# OLED_MODEL.net
KiCad netlist of a schematic drawn in Altium Designer
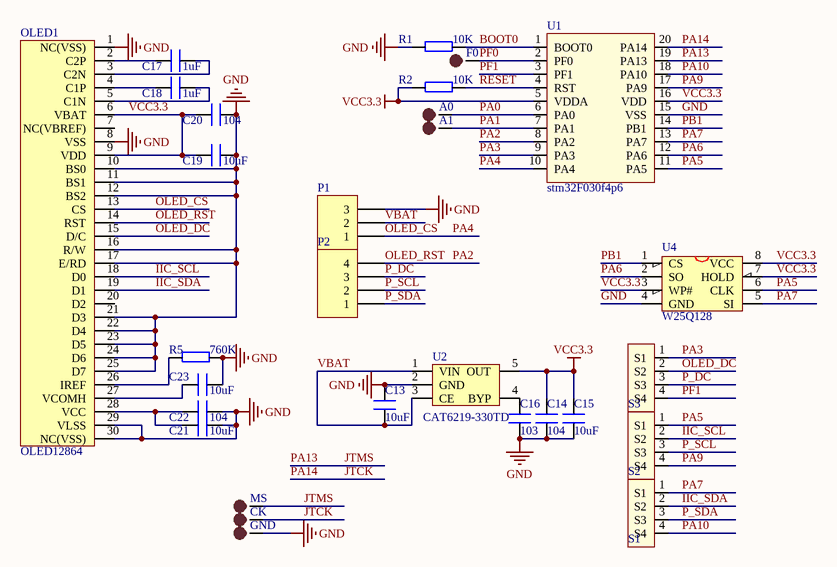
[diagram p0: OLED_MODEL.SchDoc]

(export (version "E")
  (design (tool "Eeschema 10.0.6"))
  (components
    (comp (ref "A0")
      (value "TEST POINT")
      (footprint "TP-1.5")
      (description "测试点")
      (libsource (lib "STM32F767核心板封装库") (part "TEST-POINT"))
    )
    (comp (ref "A1")
      (value "TEST POINT")
      (footprint "TP-1.5")
      (description "测试点")
      (libsource (lib "STM32F767核心板封装库") (part "TEST-POINT"))
    )
    (comp (ref "C13")
      (value "10uF")
      (footprint "C 0603_L")
      (libsource (lib "WarShip V3 STM32103封装库") (part "C"))
    )
    (comp (ref "C14")
      (value "104")
      (footprint "C 0603_L")
      (libsource (lib "WarShip V3 STM32103封装库") (part "C"))
    )
    (comp (ref "C15")
      (value "10uF")
      (footprint "C 0603_L")
      (libsource (lib "WarShip V3 STM32103封装库") (part "C"))
    )
    (comp (ref "C16")
      (value "103")
      (footprint "C 0603_L")
      (libsource (lib "WarShip V3 STM32103封装库") (part "C"))
    )
    (comp (ref "C17")
      (value "1uF")
      (footprint "C 0603_L")
      (libsource (lib "WarShip V3 STM32103封装库") (part "C"))
    )
    (comp (ref "C18")
      (value "1uF")
      (footprint "C 0603_L")
      (libsource (lib "WarShip V3 STM32103封装库") (part "C"))
    )
    (comp (ref "C19")
      (value "10uF")
      (footprint "C 0603_L")
      (libsource (lib "WarShip V3 STM32103封装库") (part "C"))
    )
    (comp (ref "C20")
      (value "104")
      (footprint "C 0603_L")
      (libsource (lib "WarShip V3 STM32103封装库") (part "C"))
    )
    (comp (ref "C21")
      (value "10uF")
      (footprint "C 0603_L")
      (libsource (lib "WarShip V3 STM32103封装库") (part "C"))
    )
    (comp (ref "C22")
      (value "104")
      (footprint "C 0603_L")
      (libsource (lib "WarShip V3 STM32103封装库") (part "C"))
    )
    (comp (ref "C23")
      (value "10uF")
      (footprint "C 0603_L")
      (libsource (lib "WarShip V3 STM32103封装库") (part "C"))
    )
    (comp (ref "CK")
      (value "TEST POINT")
      (footprint "TP-1.5")
      (description "测试点")
      (libsource (lib "STM32F767核心板封装库") (part "TEST-POINT"))
    )
    (comp (ref "F0")
      (value "TEST POINT")
      (footprint "TP-1.5")
      (description "测试点")
      (libsource (lib "STM32F767核心板封装库") (part "TEST-POINT"))
    )
    (comp (ref "GND")
      (value "TEST POINT")
      (footprint "TP-1.5")
      (description "测试点")
      (libsource (lib "STM32F767核心板封装库") (part "TEST-POINT"))
    )
    (comp (ref "MS")
      (value "TEST POINT")
      (footprint "TP-1.5")
      (description "测试点")
      (libsource (lib "STM32F767核心板封装库") (part "TEST-POINT"))
    )
    (comp (ref "OLED1")
      (value "OLED12864")
      (footprint "OLED_0.96")
      (libsource (lib "OLED模块封装库") (part "OLED12864"))
    )
    (comp (ref "P1")
      (value "Header 3")
      (footprint "HDR2.54-LI-3P")
      (description "Header, 3-Pin")
      (fields (field (name "PUBLISHER") "Altium Limited"))
      (libsource (lib "STA326_V1.7") (part "Header 3"))
    )
    (comp (ref "P2")
      (value "Header 4")
      (footprint "HDR2.54-LI-4P")
      (description "Header, 4-Pin")
      (fields (field (name "PUBLISHER") "Altium Limited"))
      (libsource (lib "STA326_V1.7") (part "Header 4"))
    )
    (comp (ref "R1")
      (value "10K")
      (footprint "R 0603_L")
      (libsource (lib "WarShip V3 STM32103封装库") (part "R"))
    )
    (comp (ref "R2")
      (value "10K")
      (footprint "R 0603_L")
      (libsource (lib "WarShip V3 STM32103封装库") (part "R"))
    )
    (comp (ref "R5")
      (value "760K")
      (footprint "R 0603_L")
      (libsource (lib "WarShip V3 STM32103封装库") (part "R"))
    )
    (comp (ref "S1")
      (value "selecter")
      (footprint "selector_4")
      (libsource (lib "oled_model") (part "selector_4"))
    )
    (comp (ref "S2")
      (value "selecter")
      (footprint "selector_4")
      (libsource (lib "oled_model") (part "selector_4"))
    )
    (comp (ref "S3")
      (value "selecter")
      (footprint "selector_4")
      (libsource (lib "oled_model") (part "selector_4"))
    )
    (comp (ref "U1")
      (value "stm32F030f4p6")
      (footprint "TSSOP20_N")
      (libsource (lib "oled_model") (part "stm32f030"))
    )
    (comp (ref "U2")
      (value "CAT6219-330TD")
      (footprint "SOT23-5N")
      (description "3.3V 500mA LDO")
      (libsource (lib "STM32H743核心板封装库") (part "CAT6219-330TD"))
    )
    (comp (ref "U4")
      (value "W25Q128")
      (footprint "SOIC-8")
      (description "W25X16;SST25VF016;MX25L1605")
      (libsource (lib "WarShip V3 STM32103封装库") (part "W25X16"))
    )
  )
  (nets
    (net (code "1") (name "/BOOT0") (class "Default")
      (node (ref "R1") (pin "1") (pintype "passive"))
      (node (ref "U1") (pin "1") (pinfunction "BOOT0_1") (pintype "passive"))
    )
    (net (code "2") (name "/IIC_SCL") (class "Default")
      (node (ref "OLED1") (pin "18") (pinfunction "D0_18") (pintype "passive"))
      (node (ref "S2") (pin "2") (pinfunction "S2_2") (pintype "passive"))
    )
    (net (code "3") (name "/IIC_SDA") (class "Default")
      (node (ref "OLED1") (pin "19") (pinfunction "D1_19") (pintype "passive"))
      (node (ref "S1") (pin "2") (pinfunction "S2_2") (pintype "passive"))
    )
    (net (code "4") (name "/JTCK") (class "Default")
      (node (ref "CK") (pin "1") (pinfunction "1_1") (pintype "passive"))
      (node (ref "U1") (pin "20") (pinfunction "PA14_20") (pintype "passive"))
    )
    (net (code "5") (name "/JTMS") (class "Default")
      (node (ref "MS") (pin "1") (pinfunction "1_1") (pintype "passive"))
      (node (ref "U1") (pin "19") (pinfunction "PA13_19") (pintype "passive"))
    )
    (net (code "6") (name "/OLED_CS") (class "Default")
      (node (ref "OLED1") (pin "13") (pinfunction "CS_13") (pintype "passive"))
      (node (ref "P1") (pin "1") (pinfunction "1_1") (pintype "passive"))
      (node (ref "U1") (pin "10") (pinfunction "PA4_10") (pintype "passive"))
    )
    (net (code "7") (name "/OLED_DC") (class "Default")
      (node (ref "OLED1") (pin "15") (pinfunction "D/C_15") (pintype "passive"))
      (node (ref "S3") (pin "2") (pinfunction "S2_2") (pintype "passive"))
    )
    (net (code "8") (name "/OLED_RST") (class "Default")
      (node (ref "OLED1") (pin "14") (pinfunction "RST_14") (pintype "passive"))
      (node (ref "P2") (pin "4") (pinfunction "4_4") (pintype "passive"))
      (node (ref "U1") (pin "8") (pinfunction "PA2_8") (pintype "passive"))
    )
    (net (code "9") (name "/PA0") (class "Default")
      (node (ref "A0") (pin "1") (pinfunction "1_1") (pintype "passive"))
      (node (ref "U1") (pin "6") (pinfunction "PA0_6") (pintype "passive"))
    )
    (net (code "10") (name "/PA1") (class "Default")
      (node (ref "A1") (pin "1") (pinfunction "1_1") (pintype "passive"))
      (node (ref "U1") (pin "7") (pinfunction "PA1_7") (pintype "passive"))
    )
    (net (code "11") (name "/PA3") (class "Default")
      (node (ref "S3") (pin "1") (pinfunction "S1_1") (pintype "passive"))
      (node (ref "U1") (pin "9") (pinfunction "PA3_9") (pintype "passive"))
    )
    (net (code "12") (name "/PA5") (class "Default")
      (node (ref "S2") (pin "1") (pinfunction "S1_1") (pintype "passive"))
      (node (ref "U1") (pin "11") (pinfunction "PA5_11") (pintype "passive"))
      (node (ref "U4") (pin "6") (pinfunction "CLK_6") (pintype "passive"))
    )
    (net (code "13") (name "/PA6") (class "Default")
      (node (ref "U1") (pin "12") (pinfunction "PA6_12") (pintype "passive"))
      (node (ref "U4") (pin "2") (pinfunction "SO_2") (pintype "passive"))
    )
    (net (code "14") (name "/PA7") (class "Default")
      (node (ref "S1") (pin "1") (pinfunction "S1_1") (pintype "passive"))
      (node (ref "U1") (pin "13") (pinfunction "PA7_13") (pintype "passive"))
      (node (ref "U4") (pin "5") (pinfunction "SI_5") (pintype "passive"))
    )
    (net (code "15") (name "/PA9") (class "Default")
      (node (ref "S2") (pin "4") (pinfunction "S4_4") (pintype "passive"))
      (node (ref "U1") (pin "17") (pinfunction "PA9_17") (pintype "passive"))
    )
    (net (code "16") (name "/PA10") (class "Default")
      (node (ref "S1") (pin "4") (pinfunction "S4_4") (pintype "passive"))
      (node (ref "U1") (pin "18") (pinfunction "PA10_18") (pintype "passive"))
    )
    (net (code "17") (name "/PB1") (class "Default")
      (node (ref "U1") (pin "14") (pinfunction "PB1_14") (pintype "passive"))
      (node (ref "U4") (pin "1") (pinfunction "CS_1") (pintype "passive"))
    )
    (net (code "18") (name "/PF0") (class "Default")
      (node (ref "F0") (pin "1") (pinfunction "1_1") (pintype "passive"))
      (node (ref "U1") (pin "2") (pinfunction "PF0_2") (pintype "passive"))
    )
    (net (code "19") (name "/PF1") (class "Default")
      (node (ref "S3") (pin "4") (pinfunction "S4_4") (pintype "passive"))
      (node (ref "U1") (pin "3") (pinfunction "PF1_3") (pintype "passive"))
    )
    (net (code "20") (name "/P_DC") (class "Default")
      (node (ref "P2") (pin "3") (pinfunction "3_3") (pintype "passive"))
      (node (ref "S3") (pin "3") (pinfunction "S3_3") (pintype "passive"))
    )
    (net (code "21") (name "/P_SCL") (class "Default")
      (node (ref "P2") (pin "2") (pinfunction "2_2") (pintype "passive"))
      (node (ref "S2") (pin "3") (pinfunction "S3_3") (pintype "passive"))
    )
    (net (code "22") (name "/P_SDA") (class "Default")
      (node (ref "P2") (pin "1") (pinfunction "1_1") (pintype "passive"))
      (node (ref "S1") (pin "3") (pinfunction "S3_3") (pintype "passive"))
    )
    (net (code "23") (name "/RESET") (class "Default")
      (node (ref "R2") (pin "1") (pintype "passive"))
      (node (ref "U1") (pin "4") (pinfunction "RST_4") (pintype "passive"))
    )
    (net (code "24") (name "/VBAT") (class "Default")
      (node (ref "C13") (pin "1") (pintype "passive"))
      (node (ref "P1") (pin "2") (pinfunction "2_2") (pintype "passive"))
      (node (ref "U2") (pin "1") (pinfunction "VIN_1") (pintype "passive"))
      (node (ref "U2") (pin "3") (pinfunction "CE_3") (pintype "passive"))
    )
    (net (code "25") (name "GND") (class "Default")
      (node (ref "C13") (pin "2") (pintype "passive"))
      (node (ref "C14") (pin "1") (pintype "passive"))
      (node (ref "C15") (pin "1") (pintype "passive"))
      (node (ref "C16") (pin "1") (pintype "passive"))
      (node (ref "C19") (pin "1") (pintype "passive"))
      (node (ref "C20") (pin "1") (pintype "passive"))
      (node (ref "C21") (pin "1") (pintype "passive"))
      (node (ref "C22") (pin "1") (pintype "passive"))
      (node (ref "C23") (pin "1") (pintype "passive"))
      (node (ref "GND") (pin "1") (pinfunction "1_1") (pintype "passive"))
      (node (ref "OLED1") (pin "1") (pinfunction "NC(VSS)_1") (pintype "passive"))
      (node (ref "OLED1") (pin "10") (pinfunction "BS0_10") (pintype "passive"))
      (node (ref "OLED1") (pin "11") (pinfunction "BS1_11") (pintype "passive"))
      (node (ref "OLED1") (pin "12") (pinfunction "BS2_12") (pintype "passive"))
      (node (ref "OLED1") (pin "16") (pinfunction "R/W_16") (pintype "passive"))
      (node (ref "OLED1") (pin "17") (pinfunction "E/RD_17") (pintype "passive"))
      (node (ref "OLED1") (pin "21") (pinfunction "D3_21") (pintype "passive"))
      (node (ref "OLED1") (pin "22") (pinfunction "D4_22") (pintype "passive"))
      (node (ref "OLED1") (pin "23") (pinfunction "D5_23") (pintype "passive"))
      (node (ref "OLED1") (pin "24") (pinfunction "D6_24") (pintype "passive"))
      (node (ref "OLED1") (pin "25") (pinfunction "D7_25") (pintype "passive"))
      (node (ref "OLED1") (pin "29") (pinfunction "VLSS_29") (pintype "passive"))
      (node (ref "OLED1") (pin "30") (pinfunction "NC(VSS)_30") (pintype "passive"))
      (node (ref "OLED1") (pin "8") (pinfunction "VSS_8") (pintype "passive"))
      (node (ref "P1") (pin "3") (pinfunction "3_3") (pintype "passive"))
      (node (ref "R1") (pin "2") (pintype "passive"))
      (node (ref "R5") (pin "1") (pintype "passive"))
      (node (ref "U1") (pin "15") (pinfunction "VSS_15") (pintype "passive"))
      (node (ref "U2") (pin "2") (pinfunction "GND_2") (pintype "passive"))
      (node (ref "U4") (pin "4") (pinfunction "GND_4") (pintype "passive"))
    )
    (net (code "26") (name "Net-(OLED1-C1N)") (class "Default")
      (node (ref "C18") (pin "1") (pintype "passive"))
      (node (ref "OLED1") (pin "5") (pinfunction "C1N_5") (pintype "passive"))
    )
    (net (code "27") (name "Net-(OLED1-C1P)") (class "Default")
      (node (ref "C18") (pin "2") (pintype "passive"))
      (node (ref "OLED1") (pin "4") (pinfunction "C1P_4") (pintype "passive"))
    )
    (net (code "28") (name "Net-(OLED1-C2N)") (class "Default")
      (node (ref "C17") (pin "1") (pintype "passive"))
      (node (ref "OLED1") (pin "3") (pinfunction "C2N_3") (pintype "passive"))
    )
    (net (code "29") (name "Net-(OLED1-C2P)") (class "Default")
      (node (ref "C17") (pin "2") (pintype "passive"))
      (node (ref "OLED1") (pin "2") (pinfunction "C2P_2") (pintype "passive"))
    )
    (net (code "30") (name "Net-(OLED1-IREF)") (class "Default")
      (node (ref "OLED1") (pin "26") (pinfunction "IREF_26") (pintype "passive"))
      (node (ref "R5") (pin "2") (pintype "passive"))
    )
    (net (code "31") (name "Net-(OLED1-VCC)") (class "Default")
      (node (ref "C21") (pin "2") (pintype "passive"))
      (node (ref "C22") (pin "2") (pintype "passive"))
      (node (ref "OLED1") (pin "28") (pinfunction "VCC_28") (pintype "passive"))
    )
    (net (code "32") (name "Net-(OLED1-VCOMH)") (class "Default")
      (node (ref "C23") (pin "2") (pintype "passive"))
      (node (ref "OLED1") (pin "27") (pinfunction "VCOMH_27") (pintype "passive"))
    )
    (net (code "33") (name "Net-(U2-BYP)") (class "Default")
      (node (ref "C16") (pin "2") (pintype "passive"))
      (node (ref "U2") (pin "4") (pinfunction "BYP_4") (pintype "passive"))
    )
    (net (code "34") (name "VCC3.3") (class "Default")
      (node (ref "C14") (pin "2") (pintype "passive"))
      (node (ref "C15") (pin "2") (pintype "passive"))
      (node (ref "C19") (pin "2") (pintype "passive"))
      (node (ref "C20") (pin "2") (pintype "passive"))
      (node (ref "OLED1") (pin "6") (pinfunction "VBAT_6") (pintype "passive"))
      (node (ref "OLED1") (pin "9") (pinfunction "VDD_9") (pintype "passive"))
      (node (ref "R2") (pin "2") (pintype "passive"))
      (node (ref "U1") (pin "16") (pinfunction "VDD_16") (pintype "passive"))
      (node (ref "U1") (pin "5") (pinfunction "VDDA_5") (pintype "passive"))
      (node (ref "U2") (pin "5") (pinfunction "OUT_5") (pintype "passive"))
      (node (ref "U4") (pin "3") (pinfunction "WP#_3") (pintype "passive"))
      (node (ref "U4") (pin "7") (pinfunction "HOLD_7") (pintype "passive"))
      (node (ref "U4") (pin "8") (pinfunction "VCC_8") (pintype "passive"))
    )
    (net (code "35") (name "unconnected-(OLED1-D2-Pad20)") (class "Default")
      (node (ref "OLED1") (pin "20") (pinfunction "D2_20") (pintype "passive"))
    )
    (net (code "36") (name "unconnected-(OLED1-NC(VBREF)-Pad7)") (class "Default")
      (node (ref "OLED1") (pin "7") (pinfunction "NC(VBREF)_7") (pintype "passive"))
    )
  )
)
